# BMS_Rev2_logic.net
KiCad netlist of a schematic drawn in EAGLE
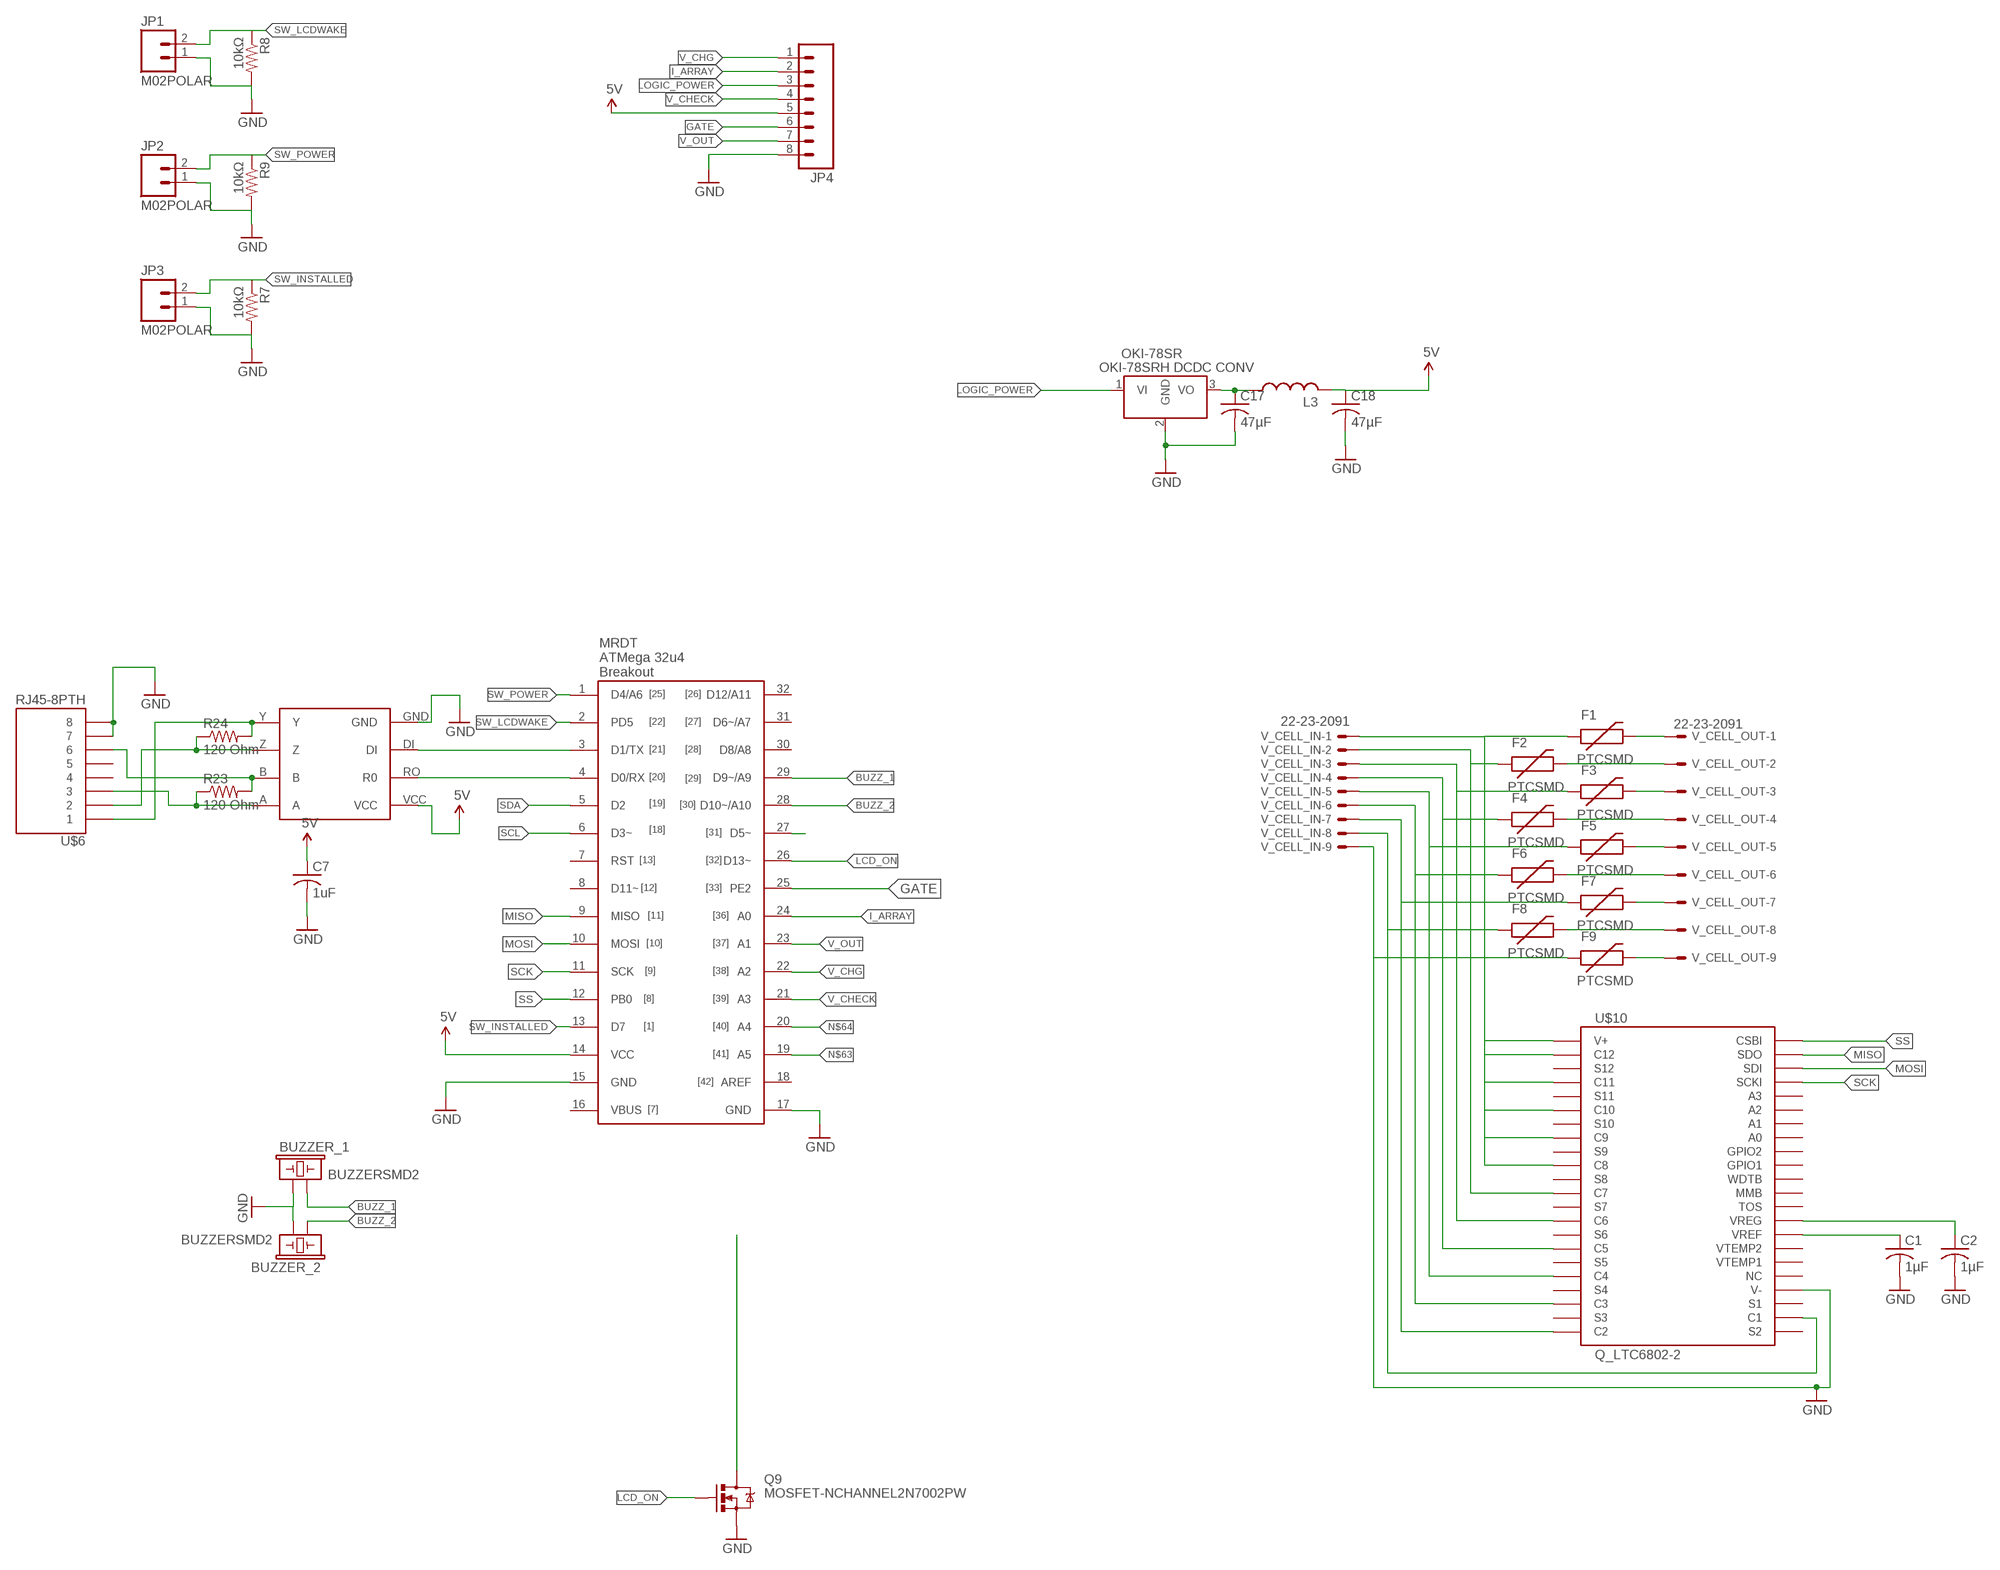
[diagram p0: schematic, sheet 1]

(export (version "E")
  (design (tool "Eeschema 10.0.6"))
  (components
    (comp (ref "BUZZER_1")
      (value "BUZZERSMD2")
      (footprint "eagle-import:BUZZER-CCV")
      (libsource (lib "eagle-import") (part "BUZZERSMD2"))
    )
    (comp (ref "BUZZER_2")
      (value "BUZZERSMD2")
      (footprint "eagle-import:BUZZER-CCV")
      (libsource (lib "eagle-import") (part "BUZZERSMD2"))
    )
    (comp (ref "C1")
      (value "1µF")
      (footprint "eagle-import:C1206")
      (libsource (lib "eagle-import") (part "C-USC1206"))
    )
    (comp (ref "C2")
      (value "1µF")
      (footprint "eagle-import:C1206")
      (libsource (lib "eagle-import") (part "C-USC1206"))
    )
    (comp (ref "C7")
      (value "1uF")
      (footprint "eagle-import:C1206")
      (libsource (lib "eagle-import") (part "C-USC1206"))
    )
    (comp (ref "C17")
      (value "47µF")
      (footprint "eagle-import:C1206")
      (libsource (lib "eagle-import") (part "C-USC1206"))
    )
    (comp (ref "C18")
      (value "47µF")
      (footprint "eagle-import:C1206")
      (libsource (lib "eagle-import") (part "C-USC1206"))
    )
    (comp (ref "F1")
      (value "PTCSMD")
      (footprint "eagle-import:PTC-1206")
      (libsource (lib "eagle-import") (part "PTCSMD"))
    )
    (comp (ref "F2")
      (value "PTCSMD")
      (footprint "eagle-import:PTC-1206")
      (libsource (lib "eagle-import") (part "PTCSMD"))
    )
    (comp (ref "F3")
      (value "PTCSMD")
      (footprint "eagle-import:PTC-1206")
      (libsource (lib "eagle-import") (part "PTCSMD"))
    )
    (comp (ref "F4")
      (value "PTCSMD")
      (footprint "eagle-import:PTC-1206")
      (libsource (lib "eagle-import") (part "PTCSMD"))
    )
    (comp (ref "F5")
      (value "PTCSMD")
      (footprint "eagle-import:PTC-1206")
      (libsource (lib "eagle-import") (part "PTCSMD"))
    )
    (comp (ref "F6")
      (value "PTCSMD")
      (footprint "eagle-import:PTC-1206")
      (libsource (lib "eagle-import") (part "PTCSMD"))
    )
    (comp (ref "F7")
      (value "PTCSMD")
      (footprint "eagle-import:PTC-1206")
      (libsource (lib "eagle-import") (part "PTCSMD"))
    )
    (comp (ref "F8")
      (value "PTCSMD")
      (footprint "eagle-import:PTC-1206")
      (libsource (lib "eagle-import") (part "PTCSMD"))
    )
    (comp (ref "F9")
      (value "PTCSMD")
      (footprint "eagle-import:PTC-1206")
      (libsource (lib "eagle-import") (part "PTCSMD"))
    )
    (comp (ref "JP1")
      (value "M02POLAR")
      (footprint "eagle-import:MOLEX-1X2")
      (libsource (lib "eagle-import") (part "M02POLAR"))
    )
    (comp (ref "JP2")
      (value "M02POLAR")
      (footprint "eagle-import:MOLEX-1X2")
      (libsource (lib "eagle-import") (part "M02POLAR"))
    )
    (comp (ref "JP3")
      (value "M02POLAR")
      (footprint "eagle-import:MOLEX-1X2")
      (libsource (lib "eagle-import") (part "M02POLAR"))
    )
    (comp (ref "JP4")
      (value "M08BM08B-SRSS-TB")
      (footprint "eagle-import:BM08B-SRSS-TB")
      (libsource (lib "eagle-import") (part "M08BM08B-SRSS-TB"))
    )
    (comp (ref "L3")
      (value "L-USL3216C")
      (footprint "eagle-import:L3216C")
      (libsource (lib "eagle-import") (part "L-USL3216C"))
    )
    (comp (ref "OKI-78SR")
      (value "Q_OKI-78SR")
      (footprint "eagle-import:OKI-78SRH")
      (libsource (lib "eagle-import") (part "Q_OKI-78SR"))
    )
    (comp (ref "Q9")
      (value "MOSFET-NCHANNEL2N7002PW")
      (footprint "eagle-import:SOT323")
      (libsource (lib "eagle-import") (part "MOSFET-NCHANNEL2N7002PW"))
    )
    (comp (ref "R7")
      (value "10kΩ")
      (footprint "eagle-import:R1206")
      (libsource (lib "eagle-import") (part "R-US_R1206"))
    )
    (comp (ref "R8")
      (value "10kΩ")
      (footprint "eagle-import:R1206")
      (libsource (lib "eagle-import") (part "R-US_R1206"))
    )
    (comp (ref "R9")
      (value "10kΩ")
      (footprint "eagle-import:R1206")
      (libsource (lib "eagle-import") (part "R-US_R1206"))
    )
    (comp (ref "R23")
      (value "120 Ohm")
      (footprint "eagle-import:1206")
      (libsource (lib "eagle-import") (part "RESISTOR1206"))
    )
    (comp (ref "R24")
      (value "120 Ohm")
      (footprint "eagle-import:1206")
      (libsource (lib "eagle-import") (part "RESISTOR1206"))
    )
    (comp (ref "U$3")
      (value "32U4_BREAKOUT")
      (footprint "eagle-import:32U4_MCU_DIP")
      (libsource (lib "eagle-import") (part "32U4_BREAKOUT"))
    )
    (comp (ref "U$6")
      (value "RJ45-8PTH")
      (footprint "eagle-import:RJ45-8")
      (libsource (lib "eagle-import") (part "RJ45-8PTH"))
    )
    (comp (ref "U$9")
      (value "MAX3077")
      (footprint "eagle-import:MAX3070E")
      (libsource (lib "eagle-import") (part "MAX3077"))
    )
    (comp (ref "U$10")
      (value "Q_LTC6802-2")
      (footprint "eagle-import:SSOP44")
      (libsource (lib "eagle-import") (part "Q_LTC6802-2"))
    )
    (comp (ref "V_CELL_IN")
      (value "22-23-2091")
      (footprint "eagle-import:22-23-2091")
      (fields (field (name "MF") "MOLEX"))
      (libsource (lib "eagle-import") (part "22-23-2091"))
    )
    (comp (ref "V_CELL_OUT")
      (value "22-23-2091")
      (footprint "eagle-import:22-23-2091")
      (fields (field (name "MF") "MOLEX"))
      (libsource (lib "eagle-import") (part "22-23-2091"))
    )
  )
  (nets
    (net (code "1") (name "5V") (class "Default")
      (node (ref "C18") (pin "1") (pinfunction "1_1") (pintype "passive"))
      (node (ref "C7") (pin "1") (pinfunction "1_1") (pintype "passive"))
      (node (ref "JP4") (pin "5") (pinfunction "5_5") (pintype "passive"))
      (node (ref "L3") (pin "2") (pinfunction "2_2") (pintype "passive"))
      (node (ref "U$3") (pin "14") (pinfunction "VCC_14") (pintype "bidirectional"))
      (node (ref "U$9") (pin "VCC") (pinfunction "VCC_VCC") (pintype "bidirectional"))
    )
    (net (code "2") (name "BUZZ_1") (class "Default")
      (node (ref "BUZZER_1") (pin "-") (pinfunction "2_-") (pintype "passive"))
      (node (ref "U$3") (pin "29") (pinfunction "D9~{/A9}_29") (pintype "bidirectional"))
    )
    (net (code "3") (name "BUZZ_2") (class "Default")
      (node (ref "BUZZER_2") (pin "+") (pinfunction "1_+") (pintype "passive"))
      (node (ref "U$3") (pin "28") (pinfunction "D10~{/A10}_28") (pintype "bidirectional"))
    )
    (net (code "4") (name "GATE") (class "Default")
      (node (ref "JP4") (pin "6") (pinfunction "6_6") (pintype "passive"))
      (node (ref "U$3") (pin "25") (pinfunction "PE2_25") (pintype "bidirectional"))
    )
    (net (code "5") (name "GND") (class "Default")
      (node (ref "BUZZER_1") (pin "+") (pinfunction "1_+") (pintype "passive"))
      (node (ref "BUZZER_2") (pin "-") (pinfunction "2_-") (pintype "passive"))
      (node (ref "C1") (pin "2") (pinfunction "2_2") (pintype "passive"))
      (node (ref "C17") (pin "2") (pinfunction "2_2") (pintype "passive"))
      (node (ref "C18") (pin "2") (pinfunction "2_2") (pintype "passive"))
      (node (ref "C2") (pin "2") (pinfunction "2_2") (pintype "passive"))
      (node (ref "C7") (pin "2") (pinfunction "2_2") (pintype "passive"))
      (node (ref "F9") (pin "1") (pinfunction "1_1") (pintype "bidirectional"))
      (node (ref "JP1") (pin "1") (pinfunction "1_1") (pintype "passive"))
      (node (ref "JP2") (pin "1") (pinfunction "1_1") (pintype "passive"))
      (node (ref "JP3") (pin "1") (pinfunction "1_1") (pintype "passive"))
      (node (ref "JP4") (pin "8") (pinfunction "8_8") (pintype "passive"))
      (node (ref "OKI-78SR") (pin "2") (pinfunction "GND_2") (pintype "bidirectional"))
      (node (ref "Q9") (pin "2") (pinfunction "S_2") (pintype "passive"))
      (node (ref "R7") (pin "2") (pinfunction "2_2") (pintype "passive"))
      (node (ref "R8") (pin "2") (pinfunction "2_2") (pintype "passive"))
      (node (ref "R9") (pin "2") (pinfunction "2_2") (pintype "passive"))
      (node (ref "U$10") (pin "26") (pinfunction "V-_26") (pintype "bidirectional"))
      (node (ref "U$3") (pin "15") (pinfunction "GND_15") (pintype "bidirectional"))
      (node (ref "U$3") (pin "17") (pinfunction "GND_17") (pintype "bidirectional"))
      (node (ref "U$6") (pin "7") (pinfunction "7_7") (pintype "bidirectional"))
      (node (ref "U$6") (pin "8") (pinfunction "8_8") (pintype "bidirectional"))
      (node (ref "U$9") (pin "GND") (pinfunction "GND_GND") (pintype "bidirectional"))
      (node (ref "V_CELL_IN") (pin "9") (pinfunction "S_9") (pintype "passive"))
    )
    (net (code "6") (name "I_ARRAY") (class "Default")
      (node (ref "JP4") (pin "2") (pinfunction "2_2") (pintype "passive"))
      (node (ref "U$3") (pin "24") (pinfunction "A0_24") (pintype "bidirectional"))
    )
    (net (code "7") (name "LCD_ON") (class "Default")
      (node (ref "Q9") (pin "1") (pinfunction "G_1") (pintype "passive"))
      (node (ref "U$3") (pin "26") (pinfunction "D13~{}_26") (pintype "bidirectional"))
    )
    (net (code "8") (name "LOGIC_POWER") (class "Default")
      (node (ref "JP4") (pin "3") (pinfunction "3_3") (pintype "passive"))
      (node (ref "OKI-78SR") (pin "1") (pinfunction "VI_1") (pintype "bidirectional"))
    )
    (net (code "9") (name "MISO") (class "Default")
      (node (ref "U$10") (pin "43") (pinfunction "SDO_43") (pintype "bidirectional"))
      (node (ref "U$3") (pin "9") (pinfunction "MISO_9") (pintype "bidirectional"))
    )
    (net (code "10") (name "MOSI") (class "Default")
      (node (ref "U$10") (pin "42") (pinfunction "SDI_42") (pintype "bidirectional"))
      (node (ref "U$3") (pin "10") (pinfunction "MOSI_10") (pintype "bidirectional"))
    )
    (net (code "11") (name "N$63") (class "Default")
      (node (ref "U$3") (pin "19") (pinfunction "A5_19") (pintype "bidirectional"))
    )
    (net (code "12") (name "N$64") (class "Default")
      (node (ref "U$3") (pin "20") (pinfunction "A4_20") (pintype "bidirectional"))
    )
    (net (code "13") (name "Net-(OKI-78SR-VO)") (class "Default")
      (node (ref "C17") (pin "1") (pinfunction "1_1") (pintype "passive"))
      (node (ref "L3") (pin "1") (pinfunction "1_1") (pintype "passive"))
      (node (ref "OKI-78SR") (pin "3") (pinfunction "VO_3") (pintype "bidirectional"))
    )
    (net (code "14") (name "Net-(R23-Pad1)") (class "Default")
      (node (ref "R23") (pin "1") (pinfunction "1_1") (pintype "passive"))
      (node (ref "U$6") (pin "3") (pinfunction "3_3") (pintype "bidirectional"))
      (node (ref "U$9") (pin "A") (pinfunction "A_A") (pintype "bidirectional"))
    )
    (net (code "15") (name "Net-(R23-Pad2)") (class "Default")
      (node (ref "R23") (pin "2") (pinfunction "2_2") (pintype "passive"))
      (node (ref "U$6") (pin "6") (pinfunction "6_6") (pintype "bidirectional"))
      (node (ref "U$9") (pin "B") (pinfunction "B_B") (pintype "bidirectional"))
    )
    (net (code "16") (name "Net-(R24-Pad1)") (class "Default")
      (node (ref "R24") (pin "1") (pinfunction "1_1") (pintype "passive"))
      (node (ref "U$6") (pin "2") (pinfunction "2_2") (pintype "bidirectional"))
      (node (ref "U$9") (pin "Z") (pinfunction "Z_Z") (pintype "bidirectional"))
    )
    (net (code "17") (name "Net-(R24-Pad2)") (class "Default")
      (node (ref "R24") (pin "2") (pinfunction "2_2") (pintype "passive"))
      (node (ref "U$6") (pin "1") (pinfunction "1_1") (pintype "bidirectional"))
      (node (ref "U$9") (pin "Y") (pinfunction "Y_Y") (pintype "bidirectional"))
    )
    (net (code "18") (name "Net-(U$3-D0{slash}RX)") (class "Default")
      (node (ref "U$3") (pin "4") (pinfunction "D0/RX_4") (pintype "bidirectional"))
      (node (ref "U$9") (pin "RO") (pinfunction "R0_RO") (pintype "bidirectional"))
    )
    (net (code "19") (name "Net-(U$3-D1{slash}TX)") (class "Default")
      (node (ref "U$3") (pin "3") (pinfunction "D1/TX_3") (pintype "bidirectional"))
      (node (ref "U$9") (pin "DI") (pinfunction "DI_DI") (pintype "bidirectional"))
    )
    (net (code "20") (name "Net-(U$10-C1)") (class "Default")
      (node (ref "F8") (pin "1") (pinfunction "1_1") (pintype "bidirectional"))
      (node (ref "U$10") (pin "24") (pinfunction "C1_24") (pintype "bidirectional"))
      (node (ref "V_CELL_IN") (pin "8") (pinfunction "S_8") (pintype "passive"))
    )
    (net (code "21") (name "Net-(U$10-C2)") (class "Default")
      (node (ref "F7") (pin "1") (pinfunction "1_1") (pintype "bidirectional"))
      (node (ref "U$10") (pin "22") (pinfunction "C2_22") (pintype "bidirectional"))
      (node (ref "V_CELL_IN") (pin "7") (pinfunction "S_7") (pintype "passive"))
    )
    (net (code "22") (name "Net-(U$10-C3)") (class "Default")
      (node (ref "F6") (pin "1") (pinfunction "1_1") (pintype "bidirectional"))
      (node (ref "U$10") (pin "20") (pinfunction "C3_20") (pintype "bidirectional"))
      (node (ref "V_CELL_IN") (pin "6") (pinfunction "S_6") (pintype "passive"))
    )
    (net (code "23") (name "Net-(U$10-C4)") (class "Default")
      (node (ref "F5") (pin "1") (pinfunction "1_1") (pintype "bidirectional"))
      (node (ref "U$10") (pin "18") (pinfunction "C4_18") (pintype "bidirectional"))
      (node (ref "V_CELL_IN") (pin "5") (pinfunction "S_5") (pintype "passive"))
    )
    (net (code "24") (name "Net-(U$10-C5)") (class "Default")
      (node (ref "F4") (pin "1") (pinfunction "1_1") (pintype "bidirectional"))
      (node (ref "U$10") (pin "16") (pinfunction "C5_16") (pintype "bidirectional"))
      (node (ref "V_CELL_IN") (pin "4") (pinfunction "S_4") (pintype "passive"))
    )
    (net (code "25") (name "Net-(U$10-C6)") (class "Default")
      (node (ref "F3") (pin "1") (pinfunction "1_1") (pintype "bidirectional"))
      (node (ref "U$10") (pin "14") (pinfunction "C6_14") (pintype "bidirectional"))
      (node (ref "V_CELL_IN") (pin "3") (pinfunction "S_3") (pintype "passive"))
    )
    (net (code "26") (name "Net-(U$10-C7)") (class "Default")
      (node (ref "F2") (pin "1") (pinfunction "1_1") (pintype "bidirectional"))
      (node (ref "U$10") (pin "12") (pinfunction "C7_12") (pintype "bidirectional"))
      (node (ref "V_CELL_IN") (pin "2") (pinfunction "S_2") (pintype "passive"))
    )
    (net (code "27") (name "Net-(U$10-C10)") (class "Default")
      (node (ref "F1") (pin "1") (pinfunction "1_1") (pintype "bidirectional"))
      (node (ref "U$10") (pin "1") (pinfunction "V+_1") (pintype "bidirectional"))
      (node (ref "U$10") (pin "10") (pinfunction "C8_10") (pintype "bidirectional"))
      (node (ref "U$10") (pin "2") (pinfunction "C12_2") (pintype "bidirectional"))
      (node (ref "U$10") (pin "4") (pinfunction "C11_4") (pintype "bidirectional"))
      (node (ref "U$10") (pin "6") (pinfunction "C10_6") (pintype "bidirectional"))
      (node (ref "U$10") (pin "8") (pinfunction "C9_8") (pintype "bidirectional"))
      (node (ref "V_CELL_IN") (pin "1") (pinfunction "S_1") (pintype "passive"))
    )
    (net (code "28") (name "Net-(U$10-VREF)") (class "Default")
      (node (ref "C1") (pin "1") (pinfunction "1_1") (pintype "passive"))
      (node (ref "U$10") (pin "30") (pinfunction "VREF_30") (pintype "bidirectional"))
    )
    (net (code "29") (name "Net-(U$10-VREG)") (class "Default")
      (node (ref "C2") (pin "1") (pinfunction "1_1") (pintype "passive"))
      (node (ref "U$10") (pin "31") (pinfunction "VREG_31") (pintype "bidirectional"))
    )
    (net (code "30") (name "Net-(V_CELL_OUTA-S)") (class "Default")
      (node (ref "F1") (pin "2") (pinfunction "2_2") (pintype "bidirectional"))
      (node (ref "V_CELL_OUT") (pin "1") (pinfunction "S_1") (pintype "passive"))
    )
    (net (code "31") (name "Net-(V_CELL_OUTB-S)") (class "Default")
      (node (ref "F2") (pin "2") (pinfunction "2_2") (pintype "bidirectional"))
      (node (ref "V_CELL_OUT") (pin "2") (pinfunction "S_2") (pintype "passive"))
    )
    (net (code "32") (name "Net-(V_CELL_OUTC-S)") (class "Default")
      (node (ref "F3") (pin "2") (pinfunction "2_2") (pintype "bidirectional"))
      (node (ref "V_CELL_OUT") (pin "3") (pinfunction "S_3") (pintype "passive"))
    )
    (net (code "33") (name "Net-(V_CELL_OUTD-S)") (class "Default")
      (node (ref "F4") (pin "2") (pinfunction "2_2") (pintype "bidirectional"))
      (node (ref "V_CELL_OUT") (pin "4") (pinfunction "S_4") (pintype "passive"))
    )
    (net (code "34") (name "Net-(V_CELL_OUTE-S)") (class "Default")
      (node (ref "F5") (pin "2") (pinfunction "2_2") (pintype "bidirectional"))
      (node (ref "V_CELL_OUT") (pin "5") (pinfunction "S_5") (pintype "passive"))
    )
    (net (code "35") (name "Net-(V_CELL_OUTF-S)") (class "Default")
      (node (ref "F6") (pin "2") (pinfunction "2_2") (pintype "bidirectional"))
      (node (ref "V_CELL_OUT") (pin "6") (pinfunction "S_6") (pintype "passive"))
    )
    (net (code "36") (name "Net-(V_CELL_OUTG-S)") (class "Default")
      (node (ref "F7") (pin "2") (pinfunction "2_2") (pintype "bidirectional"))
      (node (ref "V_CELL_OUT") (pin "7") (pinfunction "S_7") (pintype "passive"))
    )
    (net (code "37") (name "Net-(V_CELL_OUTH-S)") (class "Default")
      (node (ref "F8") (pin "2") (pinfunction "2_2") (pintype "bidirectional"))
      (node (ref "V_CELL_OUT") (pin "8") (pinfunction "S_8") (pintype "passive"))
    )
    (net (code "38") (name "Net-(V_CELL_OUTI-S)") (class "Default")
      (node (ref "F9") (pin "2") (pinfunction "2_2") (pintype "bidirectional"))
      (node (ref "V_CELL_OUT") (pin "9") (pinfunction "S_9") (pintype "passive"))
    )
    (net (code "39") (name "SCK") (class "Default")
      (node (ref "U$10") (pin "41") (pinfunction "SCKI_41") (pintype "bidirectional"))
      (node (ref "U$3") (pin "11") (pinfunction "SCK_11") (pintype "bidirectional"))
    )
    (net (code "40") (name "SCL") (class "Default")
      (node (ref "U$3") (pin "6") (pinfunction "D3~{}_6") (pintype "bidirectional"))
    )
    (net (code "41") (name "SDA") (class "Default")
      (node (ref "U$3") (pin "5") (pinfunction "D2_5") (pintype "bidirectional"))
    )
    (net (code "42") (name "SS") (class "Default")
      (node (ref "U$10") (pin "44") (pinfunction "CSBI_44") (pintype "bidirectional"))
      (node (ref "U$3") (pin "12") (pinfunction "PB0_12") (pintype "bidirectional"))
    )
    (net (code "43") (name "SW_INSTALLED") (class "Default")
      (node (ref "JP3") (pin "2") (pinfunction "2_2") (pintype "passive"))
      (node (ref "R7") (pin "1") (pinfunction "1_1") (pintype "passive"))
      (node (ref "U$3") (pin "13") (pinfunction "D7_13") (pintype "bidirectional"))
    )
    (net (code "44") (name "SW_LCDWAKE") (class "Default")
      (node (ref "JP1") (pin "2") (pinfunction "2_2") (pintype "passive"))
      (node (ref "R8") (pin "1") (pinfunction "1_1") (pintype "passive"))
      (node (ref "U$3") (pin "2") (pinfunction "PD5_2") (pintype "bidirectional"))
    )
    (net (code "45") (name "SW_POWER") (class "Default")
      (node (ref "JP2") (pin "2") (pinfunction "2_2") (pintype "passive"))
      (node (ref "R9") (pin "1") (pinfunction "1_1") (pintype "passive"))
      (node (ref "U$3") (pin "1") (pinfunction "D4/A6_1") (pintype "bidirectional"))
    )
    (net (code "46") (name "V_CHECK") (class "Default")
      (node (ref "JP4") (pin "4") (pinfunction "4_4") (pintype "passive"))
      (node (ref "U$3") (pin "21") (pinfunction "A3_21") (pintype "bidirectional"))
    )
    (net (code "47") (name "V_CHG") (class "Default")
      (node (ref "JP4") (pin "1") (pinfunction "1_1") (pintype "passive"))
      (node (ref "U$3") (pin "22") (pinfunction "A2_22") (pintype "bidirectional"))
    )
    (net (code "48") (name "V_OUT") (class "Default")
      (node (ref "JP4") (pin "7") (pinfunction "7_7") (pintype "passive"))
      (node (ref "U$3") (pin "23") (pinfunction "A1_23") (pintype "bidirectional"))
    )
    (net (code "49") (name "unconnected-(Q9-D-Pad3)") (class "Default")
      (node (ref "Q9") (pin "3") (pinfunction "D_3") (pintype "passive"))
    )
    (net (code "50") (name "unconnected-(U$3-AREF-Pad18)") (class "Default")
      (node (ref "U$3") (pin "18") (pinfunction "AREF_18") (pintype "bidirectional"))
    )
    (net (code "51") (name "unconnected-(U$3-D5~{}-Pad27)") (class "Default")
      (node (ref "U$3") (pin "27") (pinfunction "D5~{}_27") (pintype "bidirectional"))
    )
    (net (code "52") (name "unconnected-(U$3-D6~{{slash}A7}-Pad31)") (class "Default")
      (node (ref "U$3") (pin "31") (pinfunction "D6~{/A7}_31") (pintype "bidirectional"))
    )
    (net (code "53") (name "unconnected-(U$3-D8{slash}A8-Pad30)") (class "Default")
      (node (ref "U$3") (pin "30") (pinfunction "D8/A8_30") (pintype "bidirectional"))
    )
    (net (code "54") (name "unconnected-(U$3-D11~{}-Pad8)") (class "Default")
      (node (ref "U$3") (pin "8") (pinfunction "D11~{}_8") (pintype "bidirectional"))
    )
    (net (code "55") (name "unconnected-(U$3-D12{slash}A11-Pad32)") (class "Default")
      (node (ref "U$3") (pin "32") (pinfunction "D12/A11_32") (pintype "bidirectional"))
    )
    (net (code "56") (name "unconnected-(U$3-RST-Pad7)") (class "Default")
      (node (ref "U$3") (pin "7") (pinfunction "RST_7") (pintype "bidirectional"))
    )
    (net (code "57") (name "unconnected-(U$3-VBUS-Pad16)") (class "Default")
      (node (ref "U$3") (pin "16") (pinfunction "VBUS_16") (pintype "bidirectional"))
    )
    (net (code "58") (name "unconnected-(U$6-Pad4)") (class "Default")
      (node (ref "U$6") (pin "4") (pinfunction "4_4") (pintype "bidirectional"))
    )
    (net (code "59") (name "unconnected-(U$6-Pad5)") (class "Default")
      (node (ref "U$6") (pin "5") (pinfunction "5_5") (pintype "bidirectional"))
    )
    (net (code "60") (name "unconnected-(U$10-A0-Pad37)") (class "Default")
      (node (ref "U$10") (pin "37") (pinfunction "A0_37") (pintype "bidirectional"))
    )
    (net (code "61") (name "unconnected-(U$10-A1-Pad38)") (class "Default")
      (node (ref "U$10") (pin "38") (pinfunction "A1_38") (pintype "bidirectional"))
    )
    (net (code "62") (name "unconnected-(U$10-A2-Pad39)") (class "Default")
      (node (ref "U$10") (pin "39") (pinfunction "A2_39") (pintype "bidirectional"))
    )
    (net (code "63") (name "unconnected-(U$10-A3-Pad40)") (class "Default")
      (node (ref "U$10") (pin "40") (pinfunction "A3_40") (pintype "bidirectional"))
    )
    (net (code "64") (name "unconnected-(U$10-GPIO1-Pad35)") (class "Default")
      (node (ref "U$10") (pin "35") (pinfunction "GPIO1_35") (pintype "bidirectional"))
    )
    (net (code "65") (name "unconnected-(U$10-GPIO2-Pad36)") (class "Default")
      (node (ref "U$10") (pin "36") (pinfunction "GPIO2_36") (pintype "bidirectional"))
    )
    (net (code "66") (name "unconnected-(U$10-MMB-Pad33)") (class "Default")
      (node (ref "U$10") (pin "33") (pinfunction "MMB_33") (pintype "bidirectional"))
    )
    (net (code "67") (name "unconnected-(U$10-NC-Pad27)") (class "Default")
      (node (ref "U$10") (pin "27") (pinfunction "NC_27") (pintype "bidirectional"))
    )
    (net (code "68") (name "unconnected-(U$10-S1-Pad25)") (class "Default")
      (node (ref "U$10") (pin "25") (pinfunction "S1_25") (pintype "bidirectional"))
    )
    (net (code "69") (name "unconnected-(U$10-S2-Pad23)") (class "Default")
      (node (ref "U$10") (pin "23") (pinfunction "S2_23") (pintype "bidirectional"))
    )
    (net (code "70") (name "unconnected-(U$10-S3-Pad21)") (class "Default")
      (node (ref "U$10") (pin "21") (pinfunction "S3_21") (pintype "bidirectional"))
    )
    (net (code "71") (name "unconnected-(U$10-S4-Pad19)") (class "Default")
      (node (ref "U$10") (pin "19") (pinfunction "S4_19") (pintype "bidirectional"))
    )
    (net (code "72") (name "unconnected-(U$10-S5-Pad17)") (class "Default")
      (node (ref "U$10") (pin "17") (pinfunction "S5_17") (pintype "bidirectional"))
    )
    (net (code "73") (name "unconnected-(U$10-S6-Pad15)") (class "Default")
      (node (ref "U$10") (pin "15") (pinfunction "S6_15") (pintype "bidirectional"))
    )
    (net (code "74") (name "unconnected-(U$10-S7-Pad13)") (class "Default")
      (node (ref "U$10") (pin "13") (pinfunction "S7_13") (pintype "bidirectional"))
    )
    (net (code "75") (name "unconnected-(U$10-S8-Pad11)") (class "Default")
      (node (ref "U$10") (pin "11") (pinfunction "S8_11") (pintype "bidirectional"))
    )
    (net (code "76") (name "unconnected-(U$10-S9-Pad9)") (class "Default")
      (node (ref "U$10") (pin "9") (pinfunction "S9_9") (pintype "bidirectional"))
    )
    (net (code "77") (name "unconnected-(U$10-S10-Pad7)") (class "Default")
      (node (ref "U$10") (pin "7") (pinfunction "S10_7") (pintype "bidirectional"))
    )
    (net (code "78") (name "unconnected-(U$10-S11-Pad5)") (class "Default")
      (node (ref "U$10") (pin "5") (pinfunction "S11_5") (pintype "bidirectional"))
    )
    (net (code "79") (name "unconnected-(U$10-S12-Pad3)") (class "Default")
      (node (ref "U$10") (pin "3") (pinfunction "S12_3") (pintype "bidirectional"))
    )
    (net (code "80") (name "unconnected-(U$10-TOS-Pad32)") (class "Default")
      (node (ref "U$10") (pin "32") (pinfunction "TOS_32") (pintype "bidirectional"))
    )
    (net (code "81") (name "unconnected-(U$10-VTEMP1-Pad28)") (class "Default")
      (node (ref "U$10") (pin "28") (pinfunction "VTEMP1_28") (pintype "bidirectional"))
    )
    (net (code "82") (name "unconnected-(U$10-VTEMP2-Pad29)") (class "Default")
      (node (ref "U$10") (pin "29") (pinfunction "VTEMP2_29") (pintype "bidirectional"))
    )
    (net (code "83") (name "unconnected-(U$10-WDTB-Pad34)") (class "Default")
      (node (ref "U$10") (pin "34") (pinfunction "WDTB_34") (pintype "bidirectional"))
    )
  )
)
